# dash_power_supply.net
KiCad netlist of a schematic drawn in EAGLE
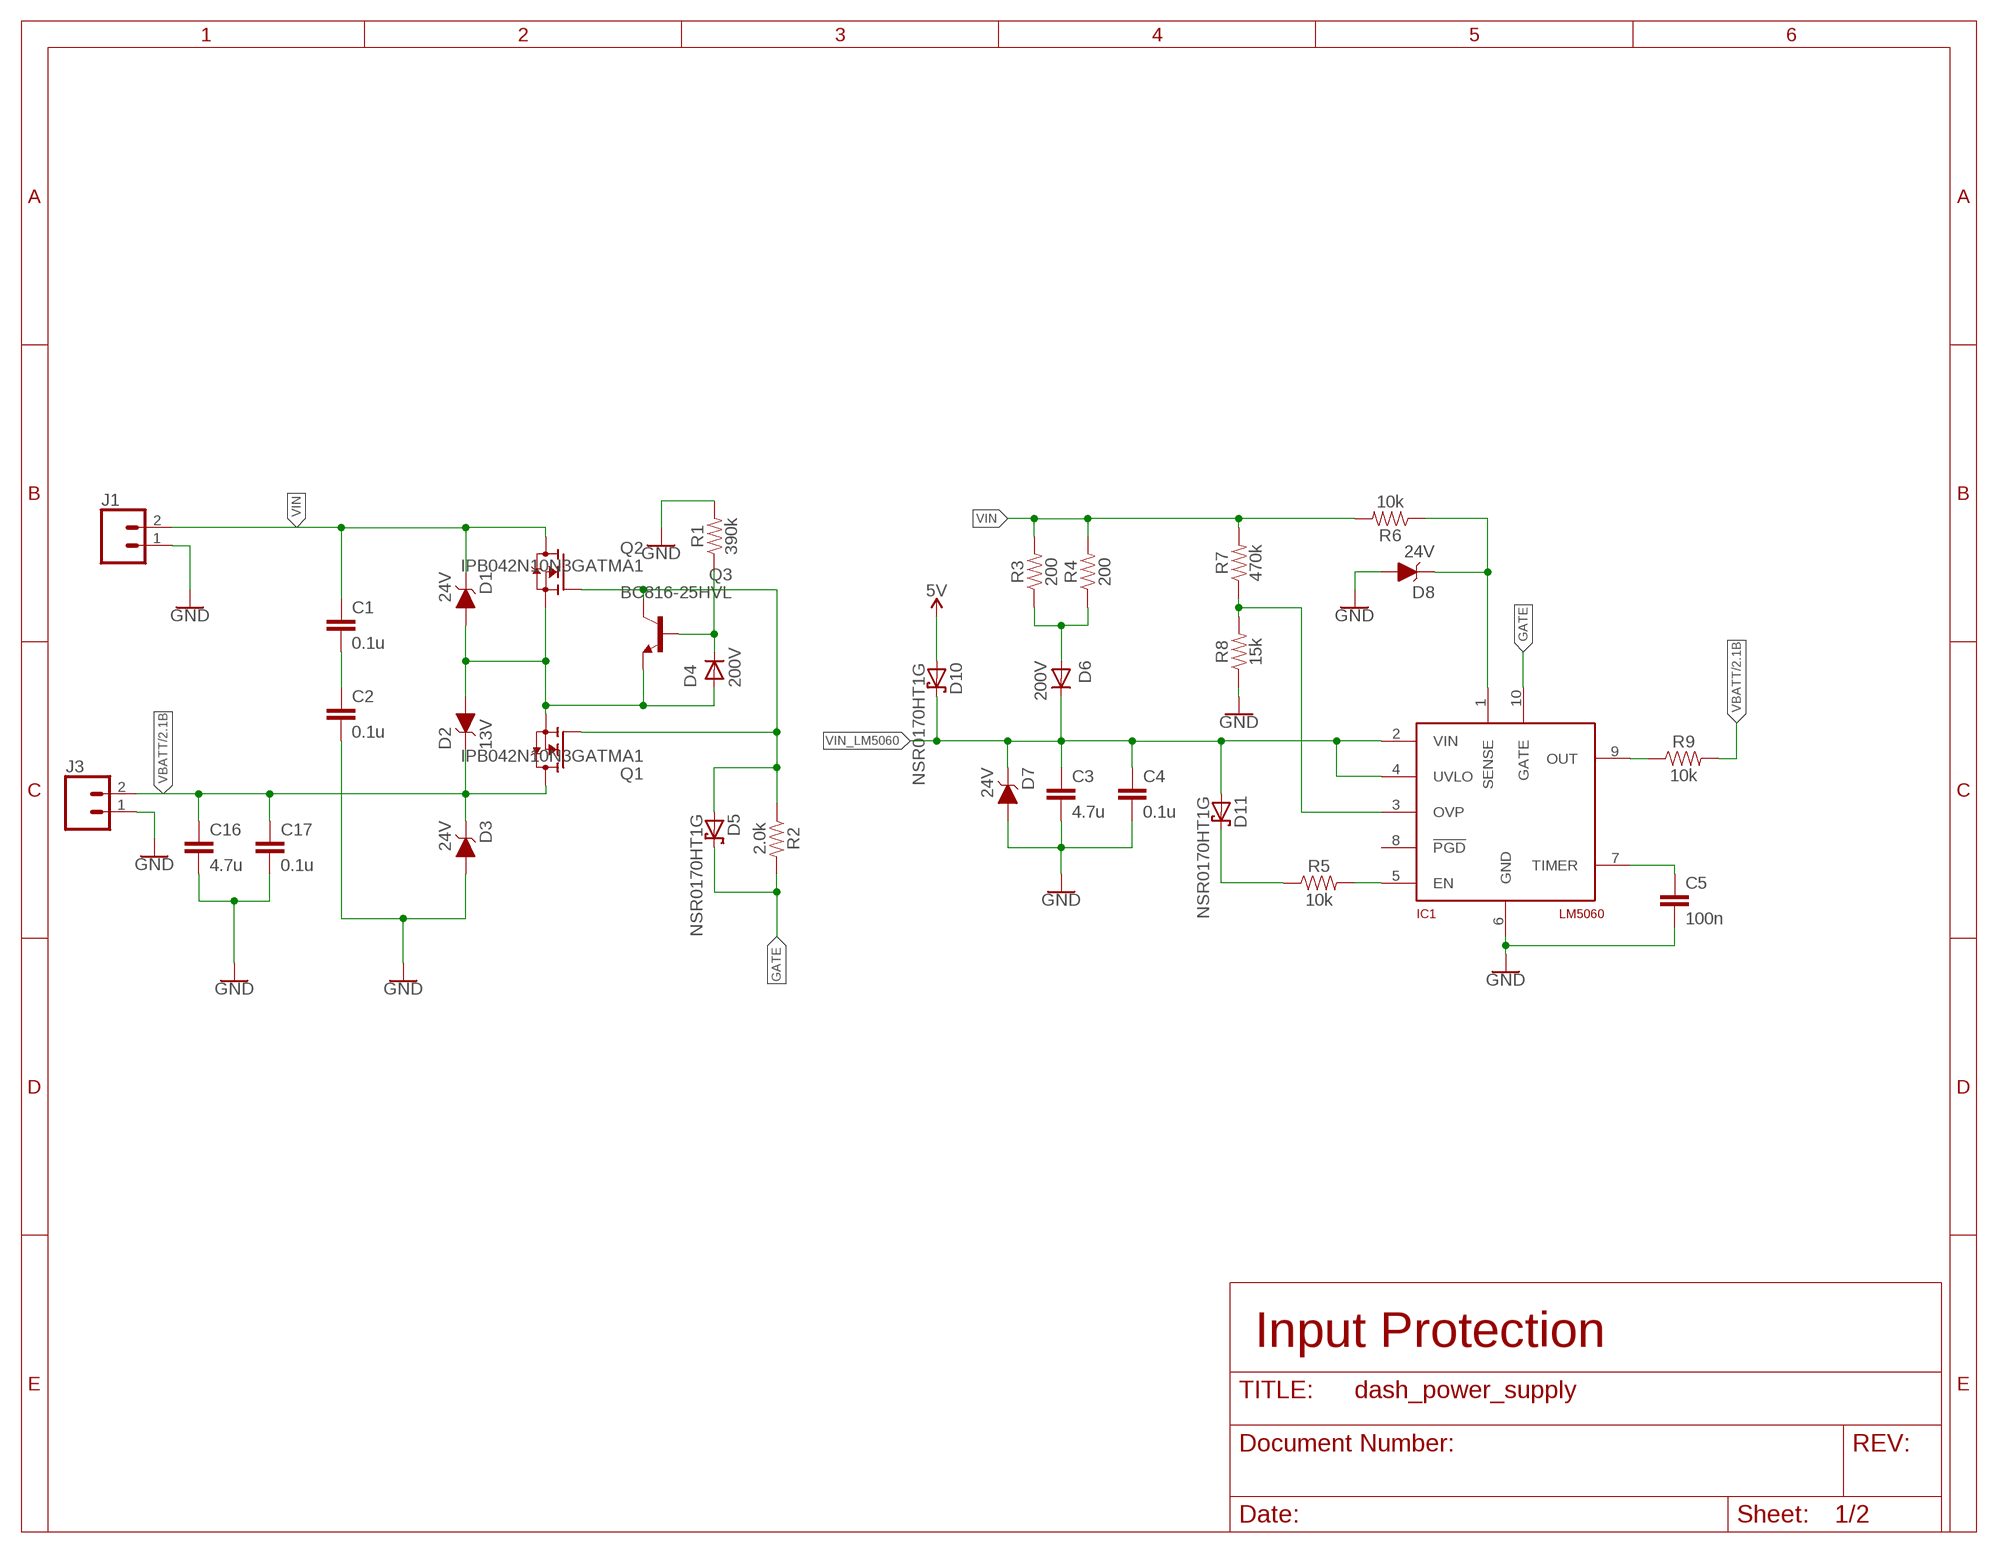
[diagram p0: schematic, sheet 1]
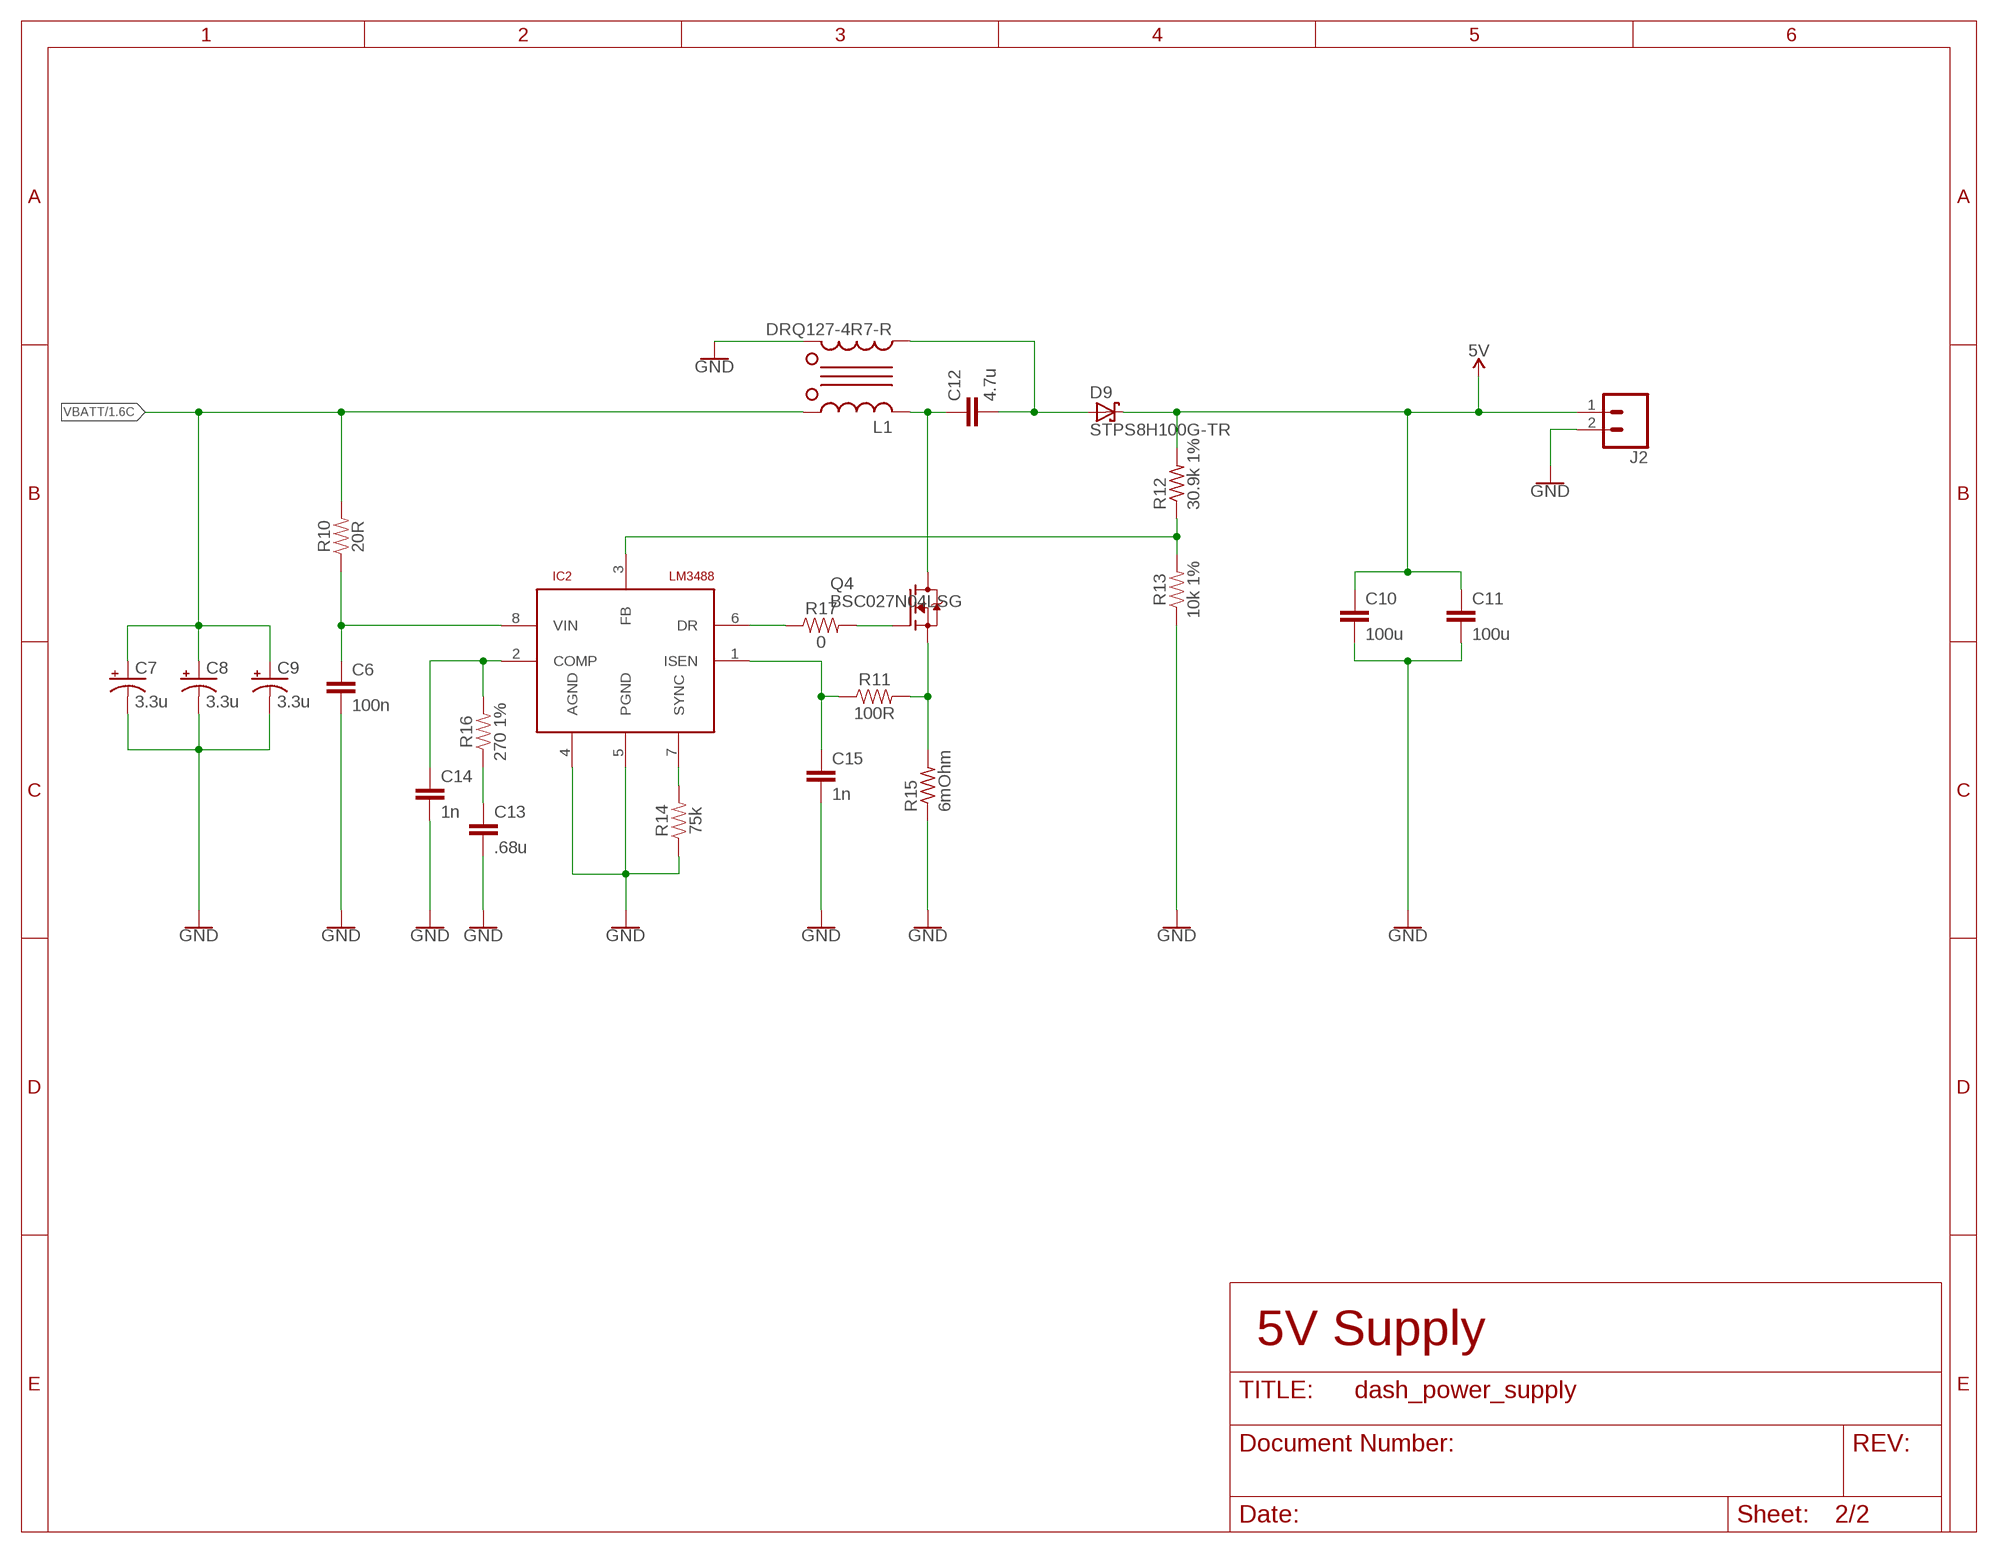
[diagram p1: schematic, sheet 2]

(export (version "E")
  (design (tool "Eeschema 10.0.6"))
  (components
    (comp (ref "C1")
      (value "0.1u")
      (footprint "eagle-import:C1210")
      (fields (field (name "VOLTAGE") "100V"))
      (libsource (lib "eagle-import") (part "CL32B104KCFNNWE"))
    )
    (comp (ref "C2")
      (value "0.1u")
      (footprint "eagle-import:C1210")
      (fields (field (name "VOLTAGE") "100V"))
      (libsource (lib "eagle-import") (part "CL32B104KCFNNWE"))
    )
    (comp (ref "C3")
      (value "4.7u")
      (footprint "eagle-import:C1210")
      (fields (field (name "VOLTAGE") "100V"))
      (libsource (lib "eagle-import") (part "CL32B475KCVZW6E"))
    )
    (comp (ref "C4")
      (value "0.1u")
      (footprint "eagle-import:C1210")
      (fields (field (name "VOLTAGE") "100V"))
      (libsource (lib "eagle-import") (part "CL32B104KCFNNWE"))
    )
    (comp (ref "C5")
      (value "100n")
      (footprint "eagle-import:0603")
      (fields (field (name "VOLTAGE") "50V"))
      (libsource (lib "eagle-import") (part "CL10B104MB8NNNC"))
    )
    (comp (ref "C16")
      (value "4.7u")
      (footprint "eagle-import:C1210")
      (fields (field (name "VOLTAGE") "100V"))
      (libsource (lib "eagle-import") (part "CL32B475KCVZW6E"))
    )
    (comp (ref "C17")
      (value "0.1u")
      (footprint "eagle-import:C1210")
      (fields (field (name "VOLTAGE") "100V"))
      (libsource (lib "eagle-import") (part "CL32B104KCFNNWE"))
    )
    (comp (ref "D1")
      (value "24V")
      (footprint "eagle-import:SMC")
      (libsource (lib "eagle-import") (part "5.0SMDJ24A"))
    )
    (comp (ref "D2")
      (value "13V")
      (footprint "eagle-import:D0-219AB")
      (libsource (lib "eagle-import") (part "PTVS13VS1UR,115"))
    )
    (comp (ref "D3")
      (value "24V")
      (footprint "eagle-import:SMC")
      (libsource (lib "eagle-import") (part "5.0SMDJ24A"))
    )
    (comp (ref "D4")
      (value "200V")
      (footprint "eagle-import:D0-219AB")
      (libsource (lib "eagle-import") (part "ES07B-GS18"))
    )
    (comp (ref "D5")
      (value "NSR0170HT1G")
      (footprint "eagle-import:SOD-323")
      (libsource (lib "eagle-import") (part "NSR0170HT1G"))
    )
    (comp (ref "D6")
      (value "200V")
      (footprint "eagle-import:D0-219AB")
      (libsource (lib "eagle-import") (part "ES07B-GS18"))
    )
    (comp (ref "D7")
      (value "24V")
      (footprint "eagle-import:SMA")
      (libsource (lib "eagle-import") (part "SZ1SMA24AT3G"))
    )
    (comp (ref "D8")
      (value "24V")
      (footprint "eagle-import:SMA")
      (libsource (lib "eagle-import") (part "SZ1SMA24AT3G"))
    )
    (comp (ref "D10")
      (value "NSR0170HT1G")
      (footprint "eagle-import:SOD-323")
      (libsource (lib "eagle-import") (part "NSR0170HT1G"))
    )
    (comp (ref "D11")
      (value "NSR0170HT1G")
      (footprint "eagle-import:SOD-323")
      (libsource (lib "eagle-import") (part "NSR0170HT1G"))
    )
    (comp (ref "IC1")
      (value "LM5060")
      (footprint "eagle-import:VSSOP-10")
      (libsource (lib "eagle-import") (part "LM5060"))
    )
    (comp (ref "J1")
      (value "CONN_02PTH4")
      (footprint "eagle-import:1X02_XTRA_BIG")
      (libsource (lib "eagle-import") (part "CONN_02PTH4"))
    )
    (comp (ref "J3")
      (value "CONN_02PTH4")
      (footprint "eagle-import:1X02_XTRA_BIG")
      (libsource (lib "eagle-import") (part "CONN_02PTH4"))
    )
    (comp (ref "Q1")
      (value "IPB042N10N3GATMA1")
      (footprint "eagle-import:TO263")
      (libsource (lib "eagle-import") (part "IPB042N10N3GATMA1"))
    )
    (comp (ref "Q2")
      (value "IPB042N10N3GATMA1")
      (footprint "eagle-import:TO263")
      (libsource (lib "eagle-import") (part "IPB042N10N3GATMA1"))
    )
    (comp (ref "Q3")
      (value "BC816-25HVL")
      (footprint "eagle-import:SOT23")
      (libsource (lib "eagle-import") (part "BC816-25HVL"))
    )
    (comp (ref "R1")
      (value "390k")
      (footprint "eagle-import:0603")
      (libsource (lib "eagle-import") (part "390KOHM-0603-1/10W-1%"))
    )
    (comp (ref "R2")
      (value "2.0k")
      (footprint "eagle-import:0603")
      (libsource (lib "eagle-import") (part "2.0KOHM-0603-1/10W-5%"))
    )
    (comp (ref "R3")
      (value "200")
      (footprint "eagle-import:1206")
      (libsource (lib "eagle-import") (part "RESISTOR1206"))
    )
    (comp (ref "R4")
      (value "200")
      (footprint "eagle-import:1206")
      (libsource (lib "eagle-import") (part "RESISTOR1206"))
    )
    (comp (ref "R5")
      (value "10k")
      (footprint "eagle-import:0603")
      (libsource (lib "eagle-import") (part "10KOHM-0603-1/10W-1%"))
    )
    (comp (ref "R6")
      (value "10k")
      (footprint "eagle-import:0603")
      (libsource (lib "eagle-import") (part "10KOHM-0603-1/10W-1%"))
    )
    (comp (ref "R7")
      (value "470k")
      (footprint "eagle-import:0603")
      (libsource (lib "eagle-import") (part "470KOHM"))
    )
    (comp (ref "R8")
      (value "15k")
      (footprint "eagle-import:0603")
      (libsource (lib "eagle-import") (part "15KOHM-0603-1/10W-1%"))
    )
    (comp (ref "R9")
      (value "10k")
      (footprint "eagle-import:0603")
      (libsource (lib "eagle-import") (part "10KOHM-0603-1/10W-1%"))
    )
    (comp (ref "C6")
      (value "100n")
      (footprint "eagle-import:0603")
      (fields (field (name "VOLTAGE") "50V"))
      (libsource (lib "eagle-import") (part "CL10B104MB8NNNC"))
    )
    (comp (ref "C7")
      (value "3.3u")
      (footprint "eagle-import:PANASONIC_C")
      (fields (field (name "VOLTAGE") "80v"))
      (libsource (lib "eagle-import") (part "EEV-FK1K3R3R"))
    )
    (comp (ref "C8")
      (value "3.3u")
      (footprint "eagle-import:PANASONIC_C")
      (fields (field (name "VOLTAGE") "80v"))
      (libsource (lib "eagle-import") (part "EEV-FK1K3R3R"))
    )
    (comp (ref "C9")
      (value "3.3u")
      (footprint "eagle-import:PANASONIC_C")
      (fields (field (name "VOLTAGE") "80v"))
      (libsource (lib "eagle-import") (part "EEV-FK1K3R3R"))
    )
    (comp (ref "C10")
      (value "100u")
      (footprint "eagle-import:C1210")
      (fields (field (name "VOLTAGE") "10V"))
      (libsource (lib "eagle-import") (part "CL32A107MPVNNNE"))
    )
    (comp (ref "C11")
      (value "100u")
      (footprint "eagle-import:C1210")
      (fields (field (name "VOLTAGE") "10V"))
      (libsource (lib "eagle-import") (part "CL32A107MPVNNNE"))
    )
    (comp (ref "C12")
      (value "4.7u")
      (footprint "eagle-import:0603")
      (fields (field (name "VOLTAGE") "35V"))
      (libsource (lib "eagle-import") (part "CL10A475KL8NRNC"))
    )
    (comp (ref "C13")
      (value ".68u")
      (footprint "eagle-import:0603")
      (fields (field (name "VOLTAGE") "16V"))
      (libsource (lib "eagle-import") (part "CL10B684KO8NFNC"))
    )
    (comp (ref "C14")
      (value "1n")
      (footprint "eagle-import:0603")
      (fields (field (name "VOLTAGE") "50V"))
      (libsource (lib "eagle-import") (part "CL10B102KB8NNWC"))
    )
    (comp (ref "C15")
      (value "1n")
      (footprint "eagle-import:0603")
      (fields (field (name "VOLTAGE") "50V"))
      (libsource (lib "eagle-import") (part "CL10B102KB8NNWC"))
    )
    (comp (ref "D9")
      (value "STPS8H100G-TR")
      (footprint "eagle-import:TO263")
      (libsource (lib "eagle-import") (part "STPS8H100G-TR"))
    )
    (comp (ref "IC2")
      (value "LM3488")
      (footprint "eagle-import:VSSOP-8")
      (libsource (lib "eagle-import") (part "LM3488"))
    )
    (comp (ref "J2")
      (value "CONN_02PTH4")
      (footprint "eagle-import:1X02_XTRA_BIG")
      (libsource (lib "eagle-import") (part "CONN_02PTH4"))
    )
    (comp (ref "L1")
      (value "DRQ127-4R7-R")
      (footprint "eagle-import:DRQ127")
      (libsource (lib "eagle-import") (part "DRQ127-4R7-R"))
    )
    (comp (ref "Q4")
      (value "BSC027N04LSG")
      (footprint "eagle-import:TDSON")
      (libsource (lib "eagle-import") (part "BSC027N04LSG"))
    )
    (comp (ref "R10")
      (value "20R")
      (footprint "eagle-import:0603")
      (libsource (lib "eagle-import") (part "RC0603JR-0720RL"))
    )
    (comp (ref "R11")
      (value "100R")
      (footprint "eagle-import:0603")
      (libsource (lib "eagle-import") (part "RC0603JR-07100RL"))
    )
    (comp (ref "R12")
      (value "30.9k 1%")
      (footprint "eagle-import:R1206")
      (fields (field (name "POWER") ".25W"))
      (libsource (lib "eagle-import") (part "RC1206FR-0730K9L"))
    )
    (comp (ref "R13")
      (value "10k 1%")
      (footprint "eagle-import:0603")
      (libsource (lib "eagle-import") (part "RC0603FR-1010KL"))
    )
    (comp (ref "R14")
      (value "75k")
      (footprint "eagle-import:0603")
      (libsource (lib "eagle-import") (part "75KOHM-0603-1/10W-1%"))
    )
    (comp (ref "R15")
      (value "6mOhm")
      (footprint "eagle-import:3216")
      (fields (field (name "POWER") "1W"))
      (libsource (lib "eagle-import") (part "PRL1632-R006-F-T1"))
    )
    (comp (ref "R16")
      (value "270 1%")
      (footprint "eagle-import:0603")
      (libsource (lib "eagle-import") (part "RC0603FR-07270RL"))
    )
    (comp (ref "R17")
      (value "0")
      (footprint "eagle-import:0603")
      (libsource (lib "eagle-import") (part "0OHM-0603-1/10W"))
    )
  )
  (nets
    (net (code "1") (name "5V") (class "Default")
      (node (ref "C10") (pin "1") (pinfunction "1_1") (pintype "passive"))
      (node (ref "C11") (pin "1") (pinfunction "1_1") (pintype "passive"))
      (node (ref "D10") (pin "A") (pinfunction "A_A") (pintype "passive"))
      (node (ref "D9") (pin "3") (pinfunction "C_3") (pintype "passive"))
      (node (ref "J2") (pin "1") (pinfunction "1_1") (pintype "passive"))
      (node (ref "R12") (pin "2") (pinfunction "2_2") (pintype "passive"))
    )
    (net (code "2") (name "GATE") (class "Default")
      (node (ref "D5") (pin "C") (pinfunction "C_C") (pintype "passive"))
      (node (ref "IC1") (pin "10") (pinfunction "GATE_10") (pintype "bidirectional"))
      (node (ref "R2") (pin "2") (pinfunction "2_2") (pintype "passive"))
    )
    (net (code "3") (name "GND") (class "Default")
      (node (ref "C10") (pin "2") (pinfunction "2_2") (pintype "passive"))
      (node (ref "C11") (pin "2") (pinfunction "2_2") (pintype "passive"))
      (node (ref "C13") (pin "2") (pinfunction "2_2") (pintype "passive"))
      (node (ref "C14") (pin "2") (pinfunction "2_2") (pintype "passive"))
      (node (ref "C15") (pin "2") (pinfunction "2_2") (pintype "passive"))
      (node (ref "C16") (pin "2") (pinfunction "2_2") (pintype "passive"))
      (node (ref "C17") (pin "2") (pinfunction "2_2") (pintype "passive"))
      (node (ref "C2") (pin "2") (pinfunction "2_2") (pintype "passive"))
      (node (ref "C3") (pin "2") (pinfunction "2_2") (pintype "passive"))
      (node (ref "C4") (pin "2") (pinfunction "2_2") (pintype "passive"))
      (node (ref "C5") (pin "2") (pinfunction "2_2") (pintype "passive"))
      (node (ref "C6") (pin "2") (pinfunction "2_2") (pintype "passive"))
      (node (ref "C7") (pin "-") (pinfunction "-_-") (pintype "passive"))
      (node (ref "C8") (pin "-") (pinfunction "-_-") (pintype "passive"))
      (node (ref "C9") (pin "-") (pinfunction "-_-") (pintype "passive"))
      (node (ref "D3") (pin "A") (pinfunction "A_A") (pintype "passive"))
      (node (ref "D7") (pin "A") (pinfunction "A_A") (pintype "passive"))
      (node (ref "D8") (pin "A") (pinfunction "A_A") (pintype "passive"))
      (node (ref "IC1") (pin "6") (pinfunction "GND_6") (pintype "bidirectional"))
      (node (ref "IC2") (pin "4") (pinfunction "AGND_4") (pintype "bidirectional"))
      (node (ref "IC2") (pin "5") (pinfunction "PGND_5") (pintype "bidirectional"))
      (node (ref "J1") (pin "1") (pinfunction "1_1") (pintype "passive"))
      (node (ref "J2") (pin "2") (pinfunction "2_2") (pintype "passive"))
      (node (ref "J3") (pin "1") (pinfunction "1_1") (pintype "passive"))
      (node (ref "L1") (pin "2") (pinfunction "2_2") (pintype "passive"))
      (node (ref "R1") (pin "2") (pinfunction "2_2") (pintype "passive"))
      (node (ref "R13") (pin "1") (pinfunction "1_1") (pintype "passive"))
      (node (ref "R14") (pin "1") (pinfunction "1_1") (pintype "passive"))
      (node (ref "R15") (pin "1") (pinfunction "1_1") (pintype "passive"))
      (node (ref "R8") (pin "1") (pinfunction "1_1") (pintype "passive"))
    )
    (net (code "4") (name "Net-(C1-Pad2)") (class "Default")
      (node (ref "C1") (pin "2") (pinfunction "2_2") (pintype "passive"))
      (node (ref "C2") (pin "1") (pinfunction "1_1") (pintype "passive"))
    )
    (net (code "5") (name "Net-(C13-Pad1)") (class "Default")
      (node (ref "C13") (pin "1") (pinfunction "1_1") (pintype "passive"))
      (node (ref "R16") (pin "1") (pinfunction "1_1") (pintype "passive"))
    )
    (net (code "6") (name "Net-(D6-PadA)") (class "Default")
      (node (ref "D6") (pin "A") (pinfunction "A_A") (pintype "passive"))
      (node (ref "R3") (pin "1") (pinfunction "1_1") (pintype "passive"))
      (node (ref "R4") (pin "1") (pinfunction "1_1") (pintype "passive"))
    )
    (net (code "7") (name "Net-(D9-A)") (class "Default")
      (node (ref "C12") (pin "2") (pinfunction "2_2") (pintype "passive"))
      (node (ref "D9") (pin "2") (pinfunction "A_2") (pintype "passive"))
      (node (ref "L1") (pin "4") (pinfunction "4_4") (pintype "passive"))
    )
    (net (code "8") (name "Net-(D11-PadC)") (class "Default")
      (node (ref "D11") (pin "C") (pinfunction "C_C") (pintype "passive"))
      (node (ref "R5") (pin "1") (pinfunction "1_1") (pintype "passive"))
    )
    (net (code "9") (name "Net-(IC1-EN)") (class "Default")
      (node (ref "IC1") (pin "5") (pinfunction "EN_5") (pintype "bidirectional"))
      (node (ref "R5") (pin "2") (pinfunction "2_2") (pintype "passive"))
    )
    (net (code "10") (name "Net-(IC1-OUT)") (class "Default")
      (node (ref "IC1") (pin "9") (pinfunction "OUT_9") (pintype "bidirectional"))
      (node (ref "R9") (pin "1") (pinfunction "1_1") (pintype "passive"))
    )
    (net (code "11") (name "Net-(IC1-OVP)") (class "Default")
      (node (ref "IC1") (pin "3") (pinfunction "OVP_3") (pintype "bidirectional"))
      (node (ref "R7") (pin "1") (pinfunction "1_1") (pintype "passive"))
      (node (ref "R8") (pin "2") (pinfunction "2_2") (pintype "passive"))
    )
    (net (code "12") (name "Net-(IC1-SENSE)") (class "Default")
      (node (ref "D8") (pin "C") (pinfunction "C_C") (pintype "passive"))
      (node (ref "IC1") (pin "1") (pinfunction "SENSE_1") (pintype "bidirectional"))
      (node (ref "R6") (pin "1") (pinfunction "1_1") (pintype "passive"))
    )
    (net (code "13") (name "Net-(IC1-TIMER)") (class "Default")
      (node (ref "C5") (pin "1") (pinfunction "1_1") (pintype "passive"))
      (node (ref "IC1") (pin "7") (pinfunction "TIMER_7") (pintype "bidirectional"))
    )
    (net (code "14") (name "Net-(IC2-COMP)") (class "Default")
      (node (ref "C14") (pin "1") (pinfunction "1_1") (pintype "passive"))
      (node (ref "IC2") (pin "2") (pinfunction "COMP_2") (pintype "bidirectional"))
      (node (ref "R16") (pin "2") (pinfunction "2_2") (pintype "passive"))
    )
    (net (code "15") (name "Net-(IC2-DR)") (class "Default")
      (node (ref "IC2") (pin "6") (pinfunction "DR_6") (pintype "bidirectional"))
      (node (ref "R17") (pin "1") (pinfunction "1_1") (pintype "passive"))
    )
    (net (code "16") (name "Net-(IC2-FB)") (class "Default")
      (node (ref "IC2") (pin "3") (pinfunction "FB_3") (pintype "bidirectional"))
      (node (ref "R12") (pin "1") (pinfunction "1_1") (pintype "passive"))
      (node (ref "R13") (pin "2") (pinfunction "2_2") (pintype "passive"))
    )
    (net (code "17") (name "Net-(IC2-ISEN)") (class "Default")
      (node (ref "C15") (pin "1") (pinfunction "1_1") (pintype "passive"))
      (node (ref "IC2") (pin "1") (pinfunction "ISEN_1") (pintype "bidirectional"))
      (node (ref "R11") (pin "1") (pinfunction "1_1") (pintype "passive"))
    )
    (net (code "18") (name "Net-(IC2-SYNC)") (class "Default")
      (node (ref "IC2") (pin "7") (pinfunction "SYNC_7") (pintype "bidirectional"))
      (node (ref "R14") (pin "2") (pinfunction "2_2") (pintype "passive"))
    )
    (net (code "19") (name "Net-(IC2-VIN)") (class "Default")
      (node (ref "C6") (pin "1") (pinfunction "1_1") (pintype "passive"))
      (node (ref "IC2") (pin "8") (pinfunction "VIN_8") (pintype "bidirectional"))
      (node (ref "R10") (pin "1") (pinfunction "1_1") (pintype "passive"))
    )
    (net (code "20") (name "Net-(Q1-G)") (class "Default")
      (node (ref "D5") (pin "A") (pinfunction "A_A") (pintype "passive"))
      (node (ref "Q1") (pin "1") (pinfunction "G_1") (pintype "passive"))
      (node (ref "Q2") (pin "1") (pinfunction "G_1") (pintype "passive"))
      (node (ref "Q3") (pin "3") (pinfunction "C_3") (pintype "passive"))
      (node (ref "R2") (pin "1") (pinfunction "1_1") (pintype "passive"))
    )
    (net (code "21") (name "Net-(Q1-S)") (class "Default")
      (node (ref "D1") (pin "A") (pinfunction "A_A") (pintype "passive"))
      (node (ref "D2") (pin "A") (pinfunction "A_A") (pintype "passive"))
      (node (ref "D4") (pin "A") (pinfunction "A_A") (pintype "passive"))
      (node (ref "Q1") (pin "2") (pinfunction "S_2") (pintype "passive"))
      (node (ref "Q2") (pin "2") (pinfunction "S_2") (pintype "passive"))
      (node (ref "Q3") (pin "2") (pinfunction "E_2") (pintype "passive"))
    )
    (net (code "22") (name "Net-(Q3-B)") (class "Default")
      (node (ref "D4") (pin "C") (pinfunction "C_C") (pintype "passive"))
      (node (ref "Q3") (pin "1") (pinfunction "B_1") (pintype "passive"))
      (node (ref "R1") (pin "1") (pinfunction "1_1") (pintype "passive"))
    )
    (net (code "23") (name "Net-(Q4-D)") (class "Default")
      (node (ref "C12") (pin "1") (pinfunction "1_1") (pintype "passive"))
      (node (ref "L1") (pin "3") (pinfunction "3_3") (pintype "passive"))
      (node (ref "Q4") (pin "5") (pinfunction "D_5") (pintype "passive"))
    )
    (net (code "24") (name "Net-(Q4-G)") (class "Default")
      (node (ref "Q4") (pin "4") (pinfunction "G_4") (pintype "passive"))
      (node (ref "R17") (pin "2") (pinfunction "2_2") (pintype "passive"))
    )
    (net (code "25") (name "Net-(Q4-S-Pad1)") (class "Default")
      (node (ref "Q4") (pin "1") (pinfunction "S_1") (pintype "passive"))
      (node (ref "Q4") (pin "2") (pinfunction "S_2") (pintype "passive"))
      (node (ref "Q4") (pin "3") (pinfunction "S_3") (pintype "passive"))
      (node (ref "R11") (pin "2") (pinfunction "2_2") (pintype "passive"))
      (node (ref "R15") (pin "2") (pinfunction "2_2") (pintype "passive"))
    )
    (net (code "26") (name "VBATT") (class "Default")
      (node (ref "C16") (pin "1") (pinfunction "1_1") (pintype "passive"))
      (node (ref "C17") (pin "1") (pinfunction "1_1") (pintype "passive"))
      (node (ref "C7") (pin "+") (pinfunction "+_+") (pintype "passive"))
      (node (ref "C8") (pin "+") (pinfunction "+_+") (pintype "passive"))
      (node (ref "C9") (pin "+") (pinfunction "+_+") (pintype "passive"))
      (node (ref "D2") (pin "C") (pinfunction "C_C") (pintype "passive"))
      (node (ref "D3") (pin "C") (pinfunction "C_C") (pintype "passive"))
      (node (ref "J3") (pin "2") (pinfunction "2_2") (pintype "passive"))
      (node (ref "L1") (pin "1") (pinfunction "1_1") (pintype "passive"))
      (node (ref "Q1") (pin "3") (pinfunction "D_3") (pintype "passive"))
      (node (ref "R10") (pin "2") (pinfunction "2_2") (pintype "passive"))
      (node (ref "R9") (pin "2") (pinfunction "2_2") (pintype "passive"))
    )
    (net (code "27") (name "VIN") (class "Default")
      (node (ref "C1") (pin "1") (pinfunction "1_1") (pintype "passive"))
      (node (ref "D1") (pin "C") (pinfunction "C_C") (pintype "passive"))
      (node (ref "J1") (pin "2") (pinfunction "2_2") (pintype "passive"))
      (node (ref "Q2") (pin "3") (pinfunction "D_3") (pintype "passive"))
      (node (ref "R3") (pin "2") (pinfunction "2_2") (pintype "passive"))
      (node (ref "R4") (pin "2") (pinfunction "2_2") (pintype "passive"))
      (node (ref "R6") (pin "2") (pinfunction "2_2") (pintype "passive"))
      (node (ref "R7") (pin "2") (pinfunction "2_2") (pintype "passive"))
    )
    (net (code "28") (name "VIN_LM5060") (class "Default")
      (node (ref "C3") (pin "1") (pinfunction "1_1") (pintype "passive"))
      (node (ref "C4") (pin "1") (pinfunction "1_1") (pintype "passive"))
      (node (ref "D10") (pin "C") (pinfunction "C_C") (pintype "passive"))
      (node (ref "D11") (pin "A") (pinfunction "A_A") (pintype "passive"))
      (node (ref "D6") (pin "C") (pinfunction "C_C") (pintype "passive"))
      (node (ref "D7") (pin "C") (pinfunction "C_C") (pintype "passive"))
      (node (ref "IC1") (pin "2") (pinfunction "VIN_2") (pintype "bidirectional"))
      (node (ref "IC1") (pin "4") (pinfunction "UVLO_4") (pintype "bidirectional"))
    )
    (net (code "29") (name "unconnected-(IC1-~{PGD}-Pad8)") (class "Default")
      (node (ref "IC1") (pin "8") (pinfunction "~{PGD}_8") (pintype "bidirectional"))
    )
  )
)
